# led_slave_1x2.net
KiCad netlist of a schematic drawn in EAGLE
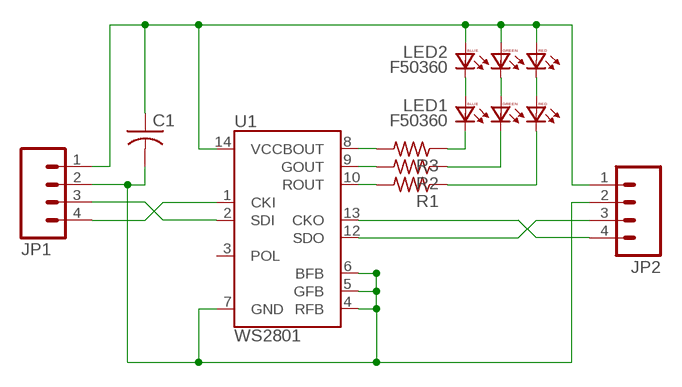
[diagram p0: schematic, sheet 1]
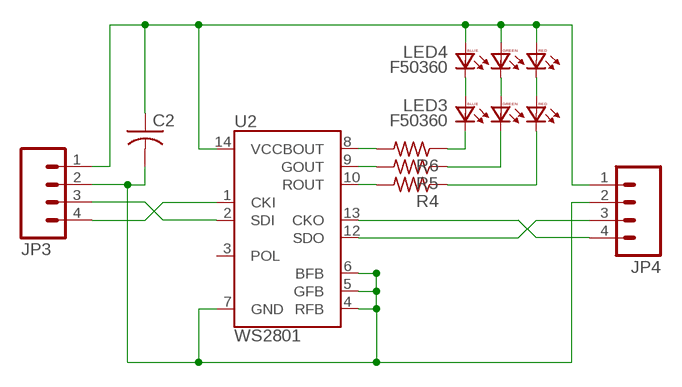
[diagram p1: schematic, sheet 2]
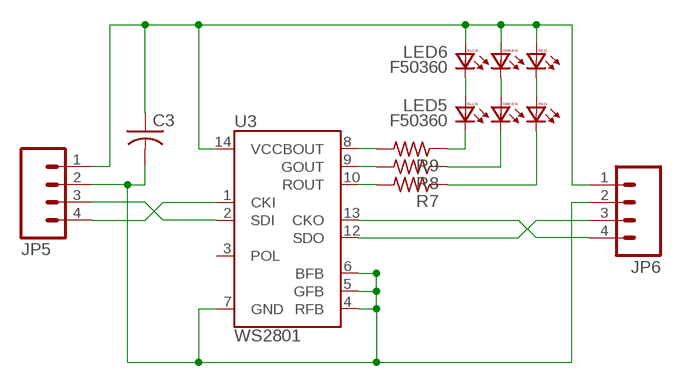
[diagram p2: schematic, sheet 3]
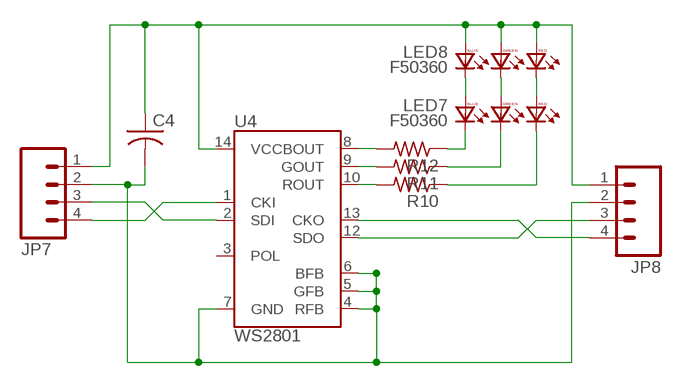
[diagram p3: schematic, sheet 4]

(export (version "E")
  (design (tool "Eeschema 10.0.6"))
  (components
    (comp (ref "C1")
      (value "C-USC1206")
      (footprint "eagle-import:C1206")
      (libsource (lib "eagle-import") (part "C-USC1206"))
    )
    (comp (ref "JP1")
      (value "M04LONGPADS")
      (footprint "eagle-import:1X04_LONGPADS")
      (libsource (lib "eagle-import") (part "M04LONGPADS"))
    )
    (comp (ref "JP2")
      (value "M04LONGPADS")
      (footprint "eagle-import:1X04_LONGPADS")
      (libsource (lib "eagle-import") (part "M04LONGPADS"))
    )
    (comp (ref "LED1")
      (value "F50360")
      (footprint "eagle-import:F50360")
      (libsource (lib "eagle-import") (part "F50360"))
    )
    (comp (ref "LED2")
      (value "F50360")
      (footprint "eagle-import:F50360")
      (libsource (lib "eagle-import") (part "F50360"))
    )
    (comp (ref "R1")
      (value "R-US_R1206")
      (footprint "eagle-import:R1206")
      (libsource (lib "eagle-import") (part "R-US_R1206"))
    )
    (comp (ref "R2")
      (value "R-US_R1206")
      (footprint "eagle-import:R1206")
      (libsource (lib "eagle-import") (part "R-US_R1206"))
    )
    (comp (ref "R3")
      (value "R-US_R1206")
      (footprint "eagle-import:R1206")
      (libsource (lib "eagle-import") (part "R-US_R1206"))
    )
    (comp (ref "U1")
      (value "WS2801")
      (footprint "eagle-import:SOP-14")
      (libsource (lib "eagle-import") (part "WS2801"))
    )
    (comp (ref "C2")
      (value "C-USC1206")
      (footprint "eagle-import:C1206")
      (libsource (lib "eagle-import") (part "C-USC1206"))
    )
    (comp (ref "JP3")
      (value "M04LONGPADS")
      (footprint "eagle-import:1X04_LONGPADS")
      (libsource (lib "eagle-import") (part "M04LONGPADS"))
    )
    (comp (ref "JP4")
      (value "M04LONGPADS")
      (footprint "eagle-import:1X04_LONGPADS")
      (libsource (lib "eagle-import") (part "M04LONGPADS"))
    )
    (comp (ref "LED3")
      (value "F50360")
      (footprint "eagle-import:F50360")
      (libsource (lib "eagle-import") (part "F50360"))
    )
    (comp (ref "LED4")
      (value "F50360")
      (footprint "eagle-import:F50360")
      (libsource (lib "eagle-import") (part "F50360"))
    )
    (comp (ref "R4")
      (value "R-US_R1206")
      (footprint "eagle-import:R1206")
      (libsource (lib "eagle-import") (part "R-US_R1206"))
    )
    (comp (ref "R5")
      (value "R-US_R1206")
      (footprint "eagle-import:R1206")
      (libsource (lib "eagle-import") (part "R-US_R1206"))
    )
    (comp (ref "R6")
      (value "R-US_R1206")
      (footprint "eagle-import:R1206")
      (libsource (lib "eagle-import") (part "R-US_R1206"))
    )
    (comp (ref "U2")
      (value "WS2801")
      (footprint "eagle-import:SOP-14")
      (libsource (lib "eagle-import") (part "WS2801"))
    )
    (comp (ref "C3")
      (value "C-USC1206")
      (footprint "eagle-import:C1206")
      (libsource (lib "eagle-import") (part "C-USC1206"))
    )
    (comp (ref "JP5")
      (value "M04LONGPADS")
      (footprint "eagle-import:1X04_LONGPADS")
      (libsource (lib "eagle-import") (part "M04LONGPADS"))
    )
    (comp (ref "JP6")
      (value "M04LONGPADS")
      (footprint "eagle-import:1X04_LONGPADS")
      (libsource (lib "eagle-import") (part "M04LONGPADS"))
    )
    (comp (ref "LED5")
      (value "F50360")
      (footprint "eagle-import:F50360")
      (libsource (lib "eagle-import") (part "F50360"))
    )
    (comp (ref "LED6")
      (value "F50360")
      (footprint "eagle-import:F50360")
      (libsource (lib "eagle-import") (part "F50360"))
    )
    (comp (ref "R7")
      (value "R-US_R1206")
      (footprint "eagle-import:R1206")
      (libsource (lib "eagle-import") (part "R-US_R1206"))
    )
    (comp (ref "R8")
      (value "R-US_R1206")
      (footprint "eagle-import:R1206")
      (libsource (lib "eagle-import") (part "R-US_R1206"))
    )
    (comp (ref "R9")
      (value "R-US_R1206")
      (footprint "eagle-import:R1206")
      (libsource (lib "eagle-import") (part "R-US_R1206"))
    )
    (comp (ref "U3")
      (value "WS2801")
      (footprint "eagle-import:SOP-14")
      (libsource (lib "eagle-import") (part "WS2801"))
    )
    (comp (ref "C4")
      (value "C-USC1206")
      (footprint "eagle-import:C1206")
      (libsource (lib "eagle-import") (part "C-USC1206"))
    )
    (comp (ref "JP7")
      (value "M04LONGPADS")
      (footprint "eagle-import:1X04_LONGPADS")
      (libsource (lib "eagle-import") (part "M04LONGPADS"))
    )
    (comp (ref "JP8")
      (value "M04LONGPADS")
      (footprint "eagle-import:1X04_LONGPADS")
      (libsource (lib "eagle-import") (part "M04LONGPADS"))
    )
    (comp (ref "LED7")
      (value "F50360")
      (footprint "eagle-import:F50360")
      (libsource (lib "eagle-import") (part "F50360"))
    )
    (comp (ref "LED8")
      (value "F50360")
      (footprint "eagle-import:F50360")
      (libsource (lib "eagle-import") (part "F50360"))
    )
    (comp (ref "R10")
      (value "R-US_R1206")
      (footprint "eagle-import:R1206")
      (libsource (lib "eagle-import") (part "R-US_R1206"))
    )
    (comp (ref "R11")
      (value "R-US_R1206")
      (footprint "eagle-import:R1206")
      (libsource (lib "eagle-import") (part "R-US_R1206"))
    )
    (comp (ref "R12")
      (value "R-US_R1206")
      (footprint "eagle-import:R1206")
      (libsource (lib "eagle-import") (part "R-US_R1206"))
    )
    (comp (ref "U4")
      (value "WS2801")
      (footprint "eagle-import:SOP-14")
      (libsource (lib "eagle-import") (part "WS2801"))
    )
  )
  (nets
    (net (code "1") (name "Net-(LED1-PadBA)") (class "Default")
      (node (ref "LED1") (pin "BA") (pinfunction "BA_BA") (pintype "passive"))
      (node (ref "LED2") (pin "BC") (pinfunction "BC_BC") (pintype "passive"))
    )
    (net (code "2") (name "Net-(LED1-PadBC)") (class "Default")
      (node (ref "LED1") (pin "BC") (pinfunction "BC_BC") (pintype "passive"))
      (node (ref "R3") (pin "1") (pinfunction "1_1") (pintype "passive"))
    )
    (net (code "3") (name "Net-(LED1-PadGA)") (class "Default")
      (node (ref "LED1") (pin "GA") (pinfunction "GA_GA") (pintype "passive"))
      (node (ref "LED2") (pin "GC") (pinfunction "GC_GC") (pintype "passive"))
    )
    (net (code "4") (name "Net-(LED1-PadGC)") (class "Default")
      (node (ref "LED1") (pin "GC") (pinfunction "GC_GC") (pintype "passive"))
      (node (ref "R2") (pin "1") (pinfunction "1_1") (pintype "passive"))
    )
    (net (code "5") (name "Net-(LED1-PadRA)") (class "Default")
      (node (ref "LED1") (pin "RA") (pinfunction "RA_RA") (pintype "passive"))
      (node (ref "LED2") (pin "RC") (pinfunction "RC_RC") (pintype "passive"))
    )
    (net (code "6") (name "Net-(LED1-PadRC)") (class "Default")
      (node (ref "LED1") (pin "RC") (pinfunction "RC_RC") (pintype "passive"))
      (node (ref "R1") (pin "1") (pinfunction "1_1") (pintype "passive"))
    )
    (net (code "7") (name "Net-(LED3-PadBA)") (class "Default")
      (node (ref "LED3") (pin "BA") (pinfunction "BA_BA") (pintype "passive"))
      (node (ref "LED4") (pin "BC") (pinfunction "BC_BC") (pintype "passive"))
    )
    (net (code "8") (name "Net-(LED3-PadBC)") (class "Default")
      (node (ref "LED3") (pin "BC") (pinfunction "BC_BC") (pintype "passive"))
      (node (ref "R6") (pin "1") (pinfunction "1_1") (pintype "passive"))
    )
    (net (code "9") (name "Net-(LED3-PadGA)") (class "Default")
      (node (ref "LED3") (pin "GA") (pinfunction "GA_GA") (pintype "passive"))
      (node (ref "LED4") (pin "GC") (pinfunction "GC_GC") (pintype "passive"))
    )
    (net (code "10") (name "Net-(LED3-PadGC)") (class "Default")
      (node (ref "LED3") (pin "GC") (pinfunction "GC_GC") (pintype "passive"))
      (node (ref "R5") (pin "1") (pinfunction "1_1") (pintype "passive"))
    )
    (net (code "11") (name "Net-(LED3-PadRA)") (class "Default")
      (node (ref "LED3") (pin "RA") (pinfunction "RA_RA") (pintype "passive"))
      (node (ref "LED4") (pin "RC") (pinfunction "RC_RC") (pintype "passive"))
    )
    (net (code "12") (name "Net-(LED3-PadRC)") (class "Default")
      (node (ref "LED3") (pin "RC") (pinfunction "RC_RC") (pintype "passive"))
      (node (ref "R4") (pin "1") (pinfunction "1_1") (pintype "passive"))
    )
    (net (code "13") (name "Net-(LED5-PadBA)") (class "Default")
      (node (ref "LED5") (pin "BA") (pinfunction "BA_BA") (pintype "passive"))
      (node (ref "LED6") (pin "BC") (pinfunction "BC_BC") (pintype "passive"))
    )
    (net (code "14") (name "Net-(LED5-PadBC)") (class "Default")
      (node (ref "LED5") (pin "BC") (pinfunction "BC_BC") (pintype "passive"))
      (node (ref "R9") (pin "1") (pinfunction "1_1") (pintype "passive"))
    )
    (net (code "15") (name "Net-(LED5-PadGA)") (class "Default")
      (node (ref "LED5") (pin "GA") (pinfunction "GA_GA") (pintype "passive"))
      (node (ref "LED6") (pin "GC") (pinfunction "GC_GC") (pintype "passive"))
    )
    (net (code "16") (name "Net-(LED5-PadGC)") (class "Default")
      (node (ref "LED5") (pin "GC") (pinfunction "GC_GC") (pintype "passive"))
      (node (ref "R8") (pin "1") (pinfunction "1_1") (pintype "passive"))
    )
    (net (code "17") (name "Net-(LED5-PadRA)") (class "Default")
      (node (ref "LED5") (pin "RA") (pinfunction "RA_RA") (pintype "passive"))
      (node (ref "LED6") (pin "RC") (pinfunction "RC_RC") (pintype "passive"))
    )
    (net (code "18") (name "Net-(LED5-PadRC)") (class "Default")
      (node (ref "LED5") (pin "RC") (pinfunction "RC_RC") (pintype "passive"))
      (node (ref "R7") (pin "1") (pinfunction "1_1") (pintype "passive"))
    )
    (net (code "19") (name "Net-(LED7-PadBA)") (class "Default")
      (node (ref "LED7") (pin "BA") (pinfunction "BA_BA") (pintype "passive"))
      (node (ref "LED8") (pin "BC") (pinfunction "BC_BC") (pintype "passive"))
    )
    (net (code "20") (name "Net-(LED7-PadBC)") (class "Default")
      (node (ref "LED7") (pin "BC") (pinfunction "BC_BC") (pintype "passive"))
      (node (ref "R12") (pin "1") (pinfunction "1_1") (pintype "passive"))
    )
    (net (code "21") (name "Net-(LED7-PadGA)") (class "Default")
      (node (ref "LED7") (pin "GA") (pinfunction "GA_GA") (pintype "passive"))
      (node (ref "LED8") (pin "GC") (pinfunction "GC_GC") (pintype "passive"))
    )
    (net (code "22") (name "Net-(LED7-PadGC)") (class "Default")
      (node (ref "LED7") (pin "GC") (pinfunction "GC_GC") (pintype "passive"))
      (node (ref "R11") (pin "1") (pinfunction "1_1") (pintype "passive"))
    )
    (net (code "23") (name "Net-(LED7-PadRA)") (class "Default")
      (node (ref "LED7") (pin "RA") (pinfunction "RA_RA") (pintype "passive"))
      (node (ref "LED8") (pin "RC") (pinfunction "RC_RC") (pintype "passive"))
    )
    (net (code "24") (name "Net-(LED7-PadRC)") (class "Default")
      (node (ref "LED7") (pin "RC") (pinfunction "RC_RC") (pintype "passive"))
      (node (ref "R10") (pin "1") (pinfunction "1_1") (pintype "passive"))
    )
    (net (code "25") (name "Net-(U1-BFB)") (class "Default")
      (node (ref "C1") (pin "2") (pinfunction "2_2") (pintype "passive"))
      (node (ref "JP1") (pin "2") (pinfunction "2_2") (pintype "passive"))
      (node (ref "JP2") (pin "2") (pinfunction "2_2") (pintype "passive"))
      (node (ref "U1") (pin "4") (pinfunction "RFB_4") (pintype "bidirectional"))
      (node (ref "U1") (pin "5") (pinfunction "GFB_5") (pintype "bidirectional"))
      (node (ref "U1") (pin "6") (pinfunction "BFB_6") (pintype "bidirectional"))
      (node (ref "U1") (pin "7") (pinfunction "GND_7") (pintype "bidirectional"))
    )
    (net (code "26") (name "Net-(U1-BOUT)") (class "Default")
      (node (ref "R3") (pin "2") (pinfunction "2_2") (pintype "passive"))
      (node (ref "U1") (pin "8") (pinfunction "BOUT_8") (pintype "bidirectional"))
    )
    (net (code "27") (name "Net-(U1-CKI)") (class "Default")
      (node (ref "JP1") (pin "4") (pinfunction "4_4") (pintype "passive"))
      (node (ref "U1") (pin "1") (pinfunction "CKI_1") (pintype "bidirectional"))
    )
    (net (code "28") (name "Net-(U1-CKO)") (class "Default")
      (node (ref "JP2") (pin "4") (pinfunction "4_4") (pintype "passive"))
      (node (ref "U1") (pin "13") (pinfunction "CKO_13") (pintype "bidirectional"))
    )
    (net (code "29") (name "Net-(U1-GOUT)") (class "Default")
      (node (ref "R2") (pin "2") (pinfunction "2_2") (pintype "passive"))
      (node (ref "U1") (pin "9") (pinfunction "GOUT_9") (pintype "bidirectional"))
    )
    (net (code "30") (name "Net-(U1-ROUT)") (class "Default")
      (node (ref "R1") (pin "2") (pinfunction "2_2") (pintype "passive"))
      (node (ref "U1") (pin "10") (pinfunction "ROUT_10") (pintype "bidirectional"))
    )
    (net (code "31") (name "Net-(U1-SDI)") (class "Default")
      (node (ref "JP1") (pin "3") (pinfunction "3_3") (pintype "passive"))
      (node (ref "U1") (pin "2") (pinfunction "SDI_2") (pintype "bidirectional"))
    )
    (net (code "32") (name "Net-(U1-SDO)") (class "Default")
      (node (ref "JP2") (pin "3") (pinfunction "3_3") (pintype "passive"))
      (node (ref "U1") (pin "12") (pinfunction "SDO_12") (pintype "bidirectional"))
    )
    (net (code "33") (name "Net-(U1-VCC)") (class "Default")
      (node (ref "C1") (pin "1") (pinfunction "1_1") (pintype "passive"))
      (node (ref "JP1") (pin "1") (pinfunction "1_1") (pintype "passive"))
      (node (ref "JP2") (pin "1") (pinfunction "1_1") (pintype "passive"))
      (node (ref "LED2") (pin "BA") (pinfunction "BA_BA") (pintype "passive"))
      (node (ref "LED2") (pin "GA") (pinfunction "GA_GA") (pintype "passive"))
      (node (ref "LED2") (pin "RA") (pinfunction "RA_RA") (pintype "passive"))
      (node (ref "U1") (pin "14") (pinfunction "VCC_14") (pintype "bidirectional"))
    )
    (net (code "34") (name "Net-(U2-BFB)") (class "Default")
      (node (ref "C2") (pin "2") (pinfunction "2_2") (pintype "passive"))
      (node (ref "JP3") (pin "2") (pinfunction "2_2") (pintype "passive"))
      (node (ref "JP4") (pin "2") (pinfunction "2_2") (pintype "passive"))
      (node (ref "U2") (pin "4") (pinfunction "RFB_4") (pintype "bidirectional"))
      (node (ref "U2") (pin "5") (pinfunction "GFB_5") (pintype "bidirectional"))
      (node (ref "U2") (pin "6") (pinfunction "BFB_6") (pintype "bidirectional"))
      (node (ref "U2") (pin "7") (pinfunction "GND_7") (pintype "bidirectional"))
    )
    (net (code "35") (name "Net-(U2-BOUT)") (class "Default")
      (node (ref "R6") (pin "2") (pinfunction "2_2") (pintype "passive"))
      (node (ref "U2") (pin "8") (pinfunction "BOUT_8") (pintype "bidirectional"))
    )
    (net (code "36") (name "Net-(U2-CKI)") (class "Default")
      (node (ref "JP3") (pin "4") (pinfunction "4_4") (pintype "passive"))
      (node (ref "U2") (pin "1") (pinfunction "CKI_1") (pintype "bidirectional"))
    )
    (net (code "37") (name "Net-(U2-CKO)") (class "Default")
      (node (ref "JP4") (pin "4") (pinfunction "4_4") (pintype "passive"))
      (node (ref "U2") (pin "13") (pinfunction "CKO_13") (pintype "bidirectional"))
    )
    (net (code "38") (name "Net-(U2-GOUT)") (class "Default")
      (node (ref "R5") (pin "2") (pinfunction "2_2") (pintype "passive"))
      (node (ref "U2") (pin "9") (pinfunction "GOUT_9") (pintype "bidirectional"))
    )
    (net (code "39") (name "Net-(U2-ROUT)") (class "Default")
      (node (ref "R4") (pin "2") (pinfunction "2_2") (pintype "passive"))
      (node (ref "U2") (pin "10") (pinfunction "ROUT_10") (pintype "bidirectional"))
    )
    (net (code "40") (name "Net-(U2-SDI)") (class "Default")
      (node (ref "JP3") (pin "3") (pinfunction "3_3") (pintype "passive"))
      (node (ref "U2") (pin "2") (pinfunction "SDI_2") (pintype "bidirectional"))
    )
    (net (code "41") (name "Net-(U2-SDO)") (class "Default")
      (node (ref "JP4") (pin "3") (pinfunction "3_3") (pintype "passive"))
      (node (ref "U2") (pin "12") (pinfunction "SDO_12") (pintype "bidirectional"))
    )
    (net (code "42") (name "Net-(U2-VCC)") (class "Default")
      (node (ref "C2") (pin "1") (pinfunction "1_1") (pintype "passive"))
      (node (ref "JP3") (pin "1") (pinfunction "1_1") (pintype "passive"))
      (node (ref "JP4") (pin "1") (pinfunction "1_1") (pintype "passive"))
      (node (ref "LED4") (pin "BA") (pinfunction "BA_BA") (pintype "passive"))
      (node (ref "LED4") (pin "GA") (pinfunction "GA_GA") (pintype "passive"))
      (node (ref "LED4") (pin "RA") (pinfunction "RA_RA") (pintype "passive"))
      (node (ref "U2") (pin "14") (pinfunction "VCC_14") (pintype "bidirectional"))
    )
    (net (code "43") (name "Net-(U3-BFB)") (class "Default")
      (node (ref "C3") (pin "2") (pinfunction "2_2") (pintype "passive"))
      (node (ref "JP5") (pin "2") (pinfunction "2_2") (pintype "passive"))
      (node (ref "JP6") (pin "2") (pinfunction "2_2") (pintype "passive"))
      (node (ref "U3") (pin "4") (pinfunction "RFB_4") (pintype "bidirectional"))
      (node (ref "U3") (pin "5") (pinfunction "GFB_5") (pintype "bidirectional"))
      (node (ref "U3") (pin "6") (pinfunction "BFB_6") (pintype "bidirectional"))
      (node (ref "U3") (pin "7") (pinfunction "GND_7") (pintype "bidirectional"))
    )
    (net (code "44") (name "Net-(U3-BOUT)") (class "Default")
      (node (ref "R9") (pin "2") (pinfunction "2_2") (pintype "passive"))
      (node (ref "U3") (pin "8") (pinfunction "BOUT_8") (pintype "bidirectional"))
    )
    (net (code "45") (name "Net-(U3-CKI)") (class "Default")
      (node (ref "JP5") (pin "4") (pinfunction "4_4") (pintype "passive"))
      (node (ref "U3") (pin "1") (pinfunction "CKI_1") (pintype "bidirectional"))
    )
    (net (code "46") (name "Net-(U3-CKO)") (class "Default")
      (node (ref "JP6") (pin "4") (pinfunction "4_4") (pintype "passive"))
      (node (ref "U3") (pin "13") (pinfunction "CKO_13") (pintype "bidirectional"))
    )
    (net (code "47") (name "Net-(U3-GOUT)") (class "Default")
      (node (ref "R8") (pin "2") (pinfunction "2_2") (pintype "passive"))
      (node (ref "U3") (pin "9") (pinfunction "GOUT_9") (pintype "bidirectional"))
    )
    (net (code "48") (name "Net-(U3-ROUT)") (class "Default")
      (node (ref "R7") (pin "2") (pinfunction "2_2") (pintype "passive"))
      (node (ref "U3") (pin "10") (pinfunction "ROUT_10") (pintype "bidirectional"))
    )
    (net (code "49") (name "Net-(U3-SDI)") (class "Default")
      (node (ref "JP5") (pin "3") (pinfunction "3_3") (pintype "passive"))
      (node (ref "U3") (pin "2") (pinfunction "SDI_2") (pintype "bidirectional"))
    )
    (net (code "50") (name "Net-(U3-SDO)") (class "Default")
      (node (ref "JP6") (pin "3") (pinfunction "3_3") (pintype "passive"))
      (node (ref "U3") (pin "12") (pinfunction "SDO_12") (pintype "bidirectional"))
    )
    (net (code "51") (name "Net-(U3-VCC)") (class "Default")
      (node (ref "C3") (pin "1") (pinfunction "1_1") (pintype "passive"))
      (node (ref "JP5") (pin "1") (pinfunction "1_1") (pintype "passive"))
      (node (ref "JP6") (pin "1") (pinfunction "1_1") (pintype "passive"))
      (node (ref "LED6") (pin "BA") (pinfunction "BA_BA") (pintype "passive"))
      (node (ref "LED6") (pin "GA") (pinfunction "GA_GA") (pintype "passive"))
      (node (ref "LED6") (pin "RA") (pinfunction "RA_RA") (pintype "passive"))
      (node (ref "U3") (pin "14") (pinfunction "VCC_14") (pintype "bidirectional"))
    )
    (net (code "52") (name "Net-(U4-BFB)") (class "Default")
      (node (ref "C4") (pin "2") (pinfunction "2_2") (pintype "passive"))
      (node (ref "JP7") (pin "2") (pinfunction "2_2") (pintype "passive"))
      (node (ref "JP8") (pin "2") (pinfunction "2_2") (pintype "passive"))
      (node (ref "U4") (pin "4") (pinfunction "RFB_4") (pintype "bidirectional"))
      (node (ref "U4") (pin "5") (pinfunction "GFB_5") (pintype "bidirectional"))
      (node (ref "U4") (pin "6") (pinfunction "BFB_6") (pintype "bidirectional"))
      (node (ref "U4") (pin "7") (pinfunction "GND_7") (pintype "bidirectional"))
    )
    (net (code "53") (name "Net-(U4-BOUT)") (class "Default")
      (node (ref "R12") (pin "2") (pinfunction "2_2") (pintype "passive"))
      (node (ref "U4") (pin "8") (pinfunction "BOUT_8") (pintype "bidirectional"))
    )
    (net (code "54") (name "Net-(U4-CKI)") (class "Default")
      (node (ref "JP7") (pin "4") (pinfunction "4_4") (pintype "passive"))
      (node (ref "U4") (pin "1") (pinfunction "CKI_1") (pintype "bidirectional"))
    )
    (net (code "55") (name "Net-(U4-CKO)") (class "Default")
      (node (ref "JP8") (pin "4") (pinfunction "4_4") (pintype "passive"))
      (node (ref "U4") (pin "13") (pinfunction "CKO_13") (pintype "bidirectional"))
    )
    (net (code "56") (name "Net-(U4-GOUT)") (class "Default")
      (node (ref "R11") (pin "2") (pinfunction "2_2") (pintype "passive"))
      (node (ref "U4") (pin "9") (pinfunction "GOUT_9") (pintype "bidirectional"))
    )
    (net (code "57") (name "Net-(U4-ROUT)") (class "Default")
      (node (ref "R10") (pin "2") (pinfunction "2_2") (pintype "passive"))
      (node (ref "U4") (pin "10") (pinfunction "ROUT_10") (pintype "bidirectional"))
    )
    (net (code "58") (name "Net-(U4-SDI)") (class "Default")
      (node (ref "JP7") (pin "3") (pinfunction "3_3") (pintype "passive"))
      (node (ref "U4") (pin "2") (pinfunction "SDI_2") (pintype "bidirectional"))
    )
    (net (code "59") (name "Net-(U4-SDO)") (class "Default")
      (node (ref "JP8") (pin "3") (pinfunction "3_3") (pintype "passive"))
      (node (ref "U4") (pin "12") (pinfunction "SDO_12") (pintype "bidirectional"))
    )
    (net (code "60") (name "Net-(U4-VCC)") (class "Default")
      (node (ref "C4") (pin "1") (pinfunction "1_1") (pintype "passive"))
      (node (ref "JP7") (pin "1") (pinfunction "1_1") (pintype "passive"))
      (node (ref "JP8") (pin "1") (pinfunction "1_1") (pintype "passive"))
      (node (ref "LED8") (pin "BA") (pinfunction "BA_BA") (pintype "passive"))
      (node (ref "LED8") (pin "GA") (pinfunction "GA_GA") (pintype "passive"))
      (node (ref "LED8") (pin "RA") (pinfunction "RA_RA") (pintype "passive"))
      (node (ref "U4") (pin "14") (pinfunction "VCC_14") (pintype "bidirectional"))
    )
    (net (code "61") (name "unconnected-(U1-POL-Pad3)") (class "Default")
      (node (ref "U1") (pin "3") (pinfunction "POL_3") (pintype "bidirectional"))
    )
    (net (code "62") (name "unconnected-(U2-POL-Pad3)") (class "Default")
      (node (ref "U2") (pin "3") (pinfunction "POL_3") (pintype "bidirectional"))
    )
    (net (code "63") (name "unconnected-(U3-POL-Pad3)") (class "Default")
      (node (ref "U3") (pin "3") (pinfunction "POL_3") (pintype "bidirectional"))
    )
    (net (code "64") (name "unconnected-(U4-POL-Pad3)") (class "Default")
      (node (ref "U4") (pin "3") (pinfunction "POL_3") (pintype "bidirectional"))
    )
  )
)
